# Test_Bench.net
KiCad netlist of a schematic drawn in EAGLE
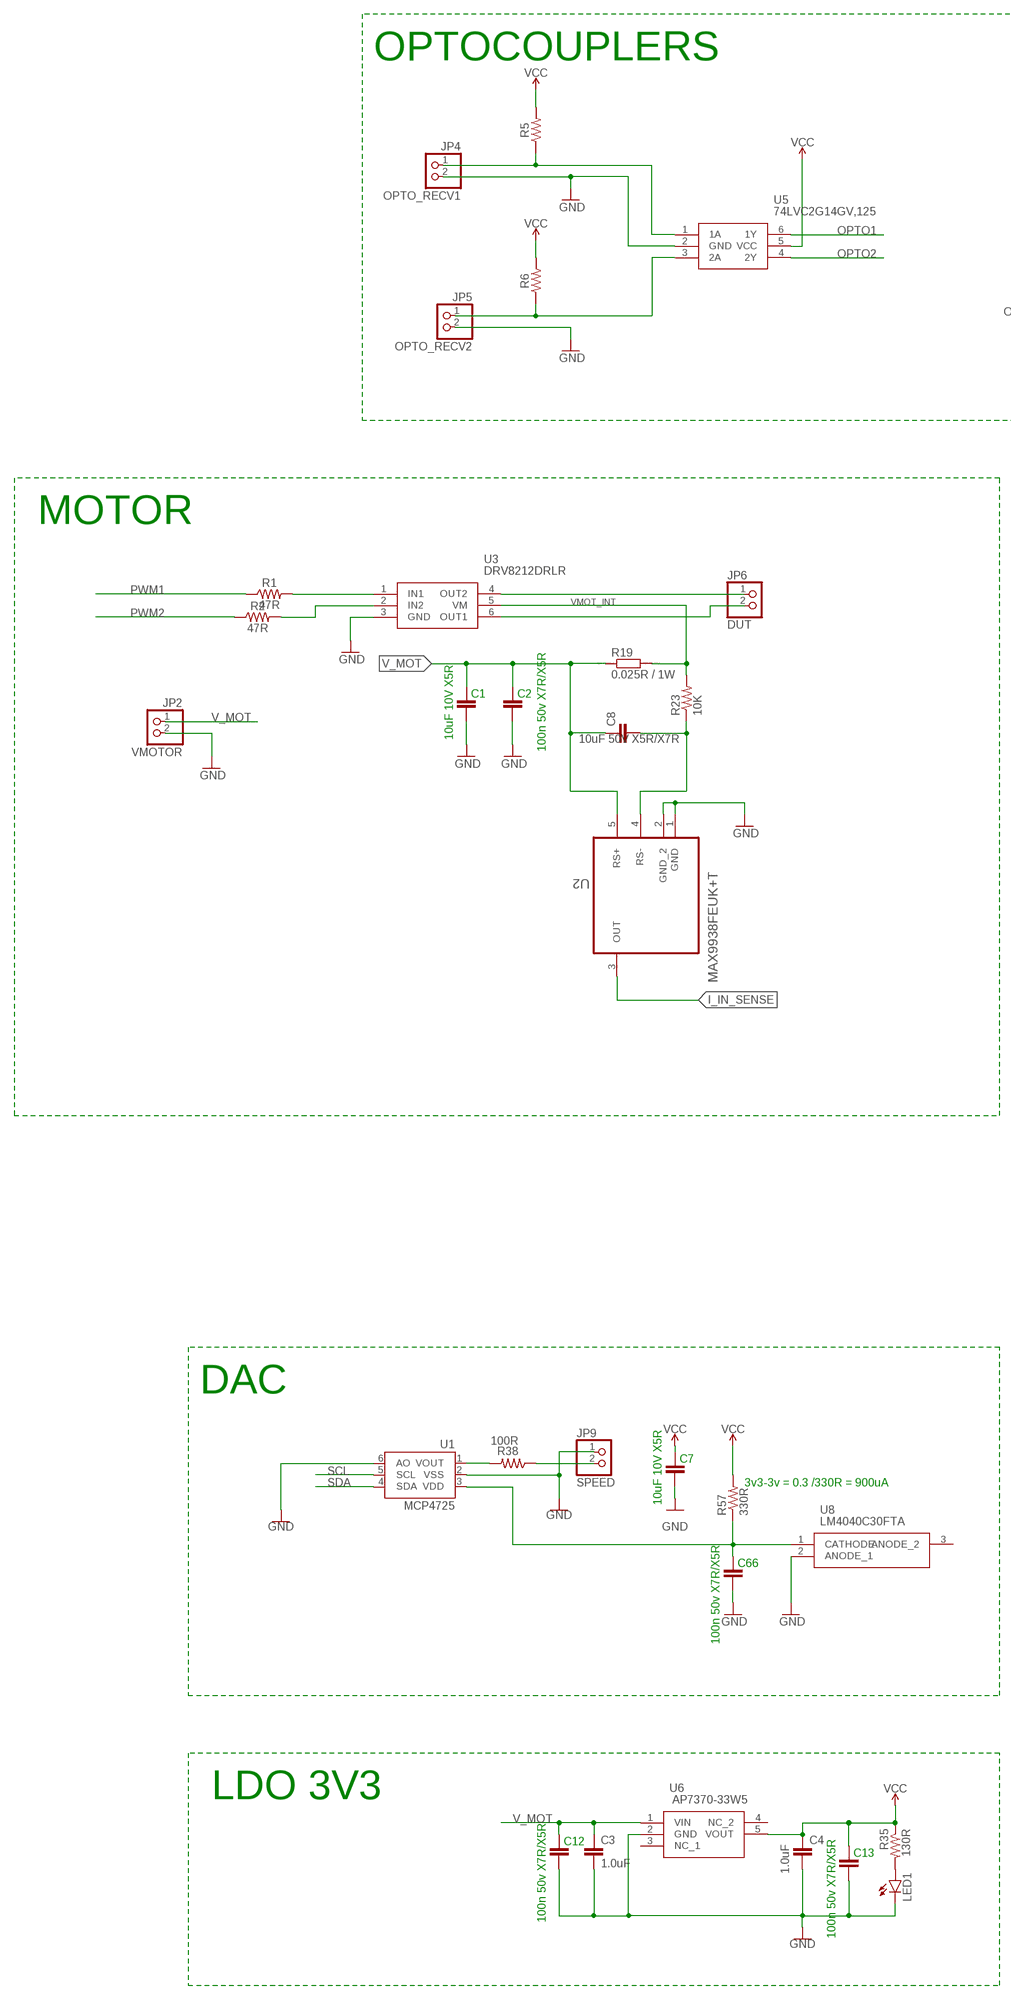
[diagram p0: schematic, sheet 1, part 1 of 2]
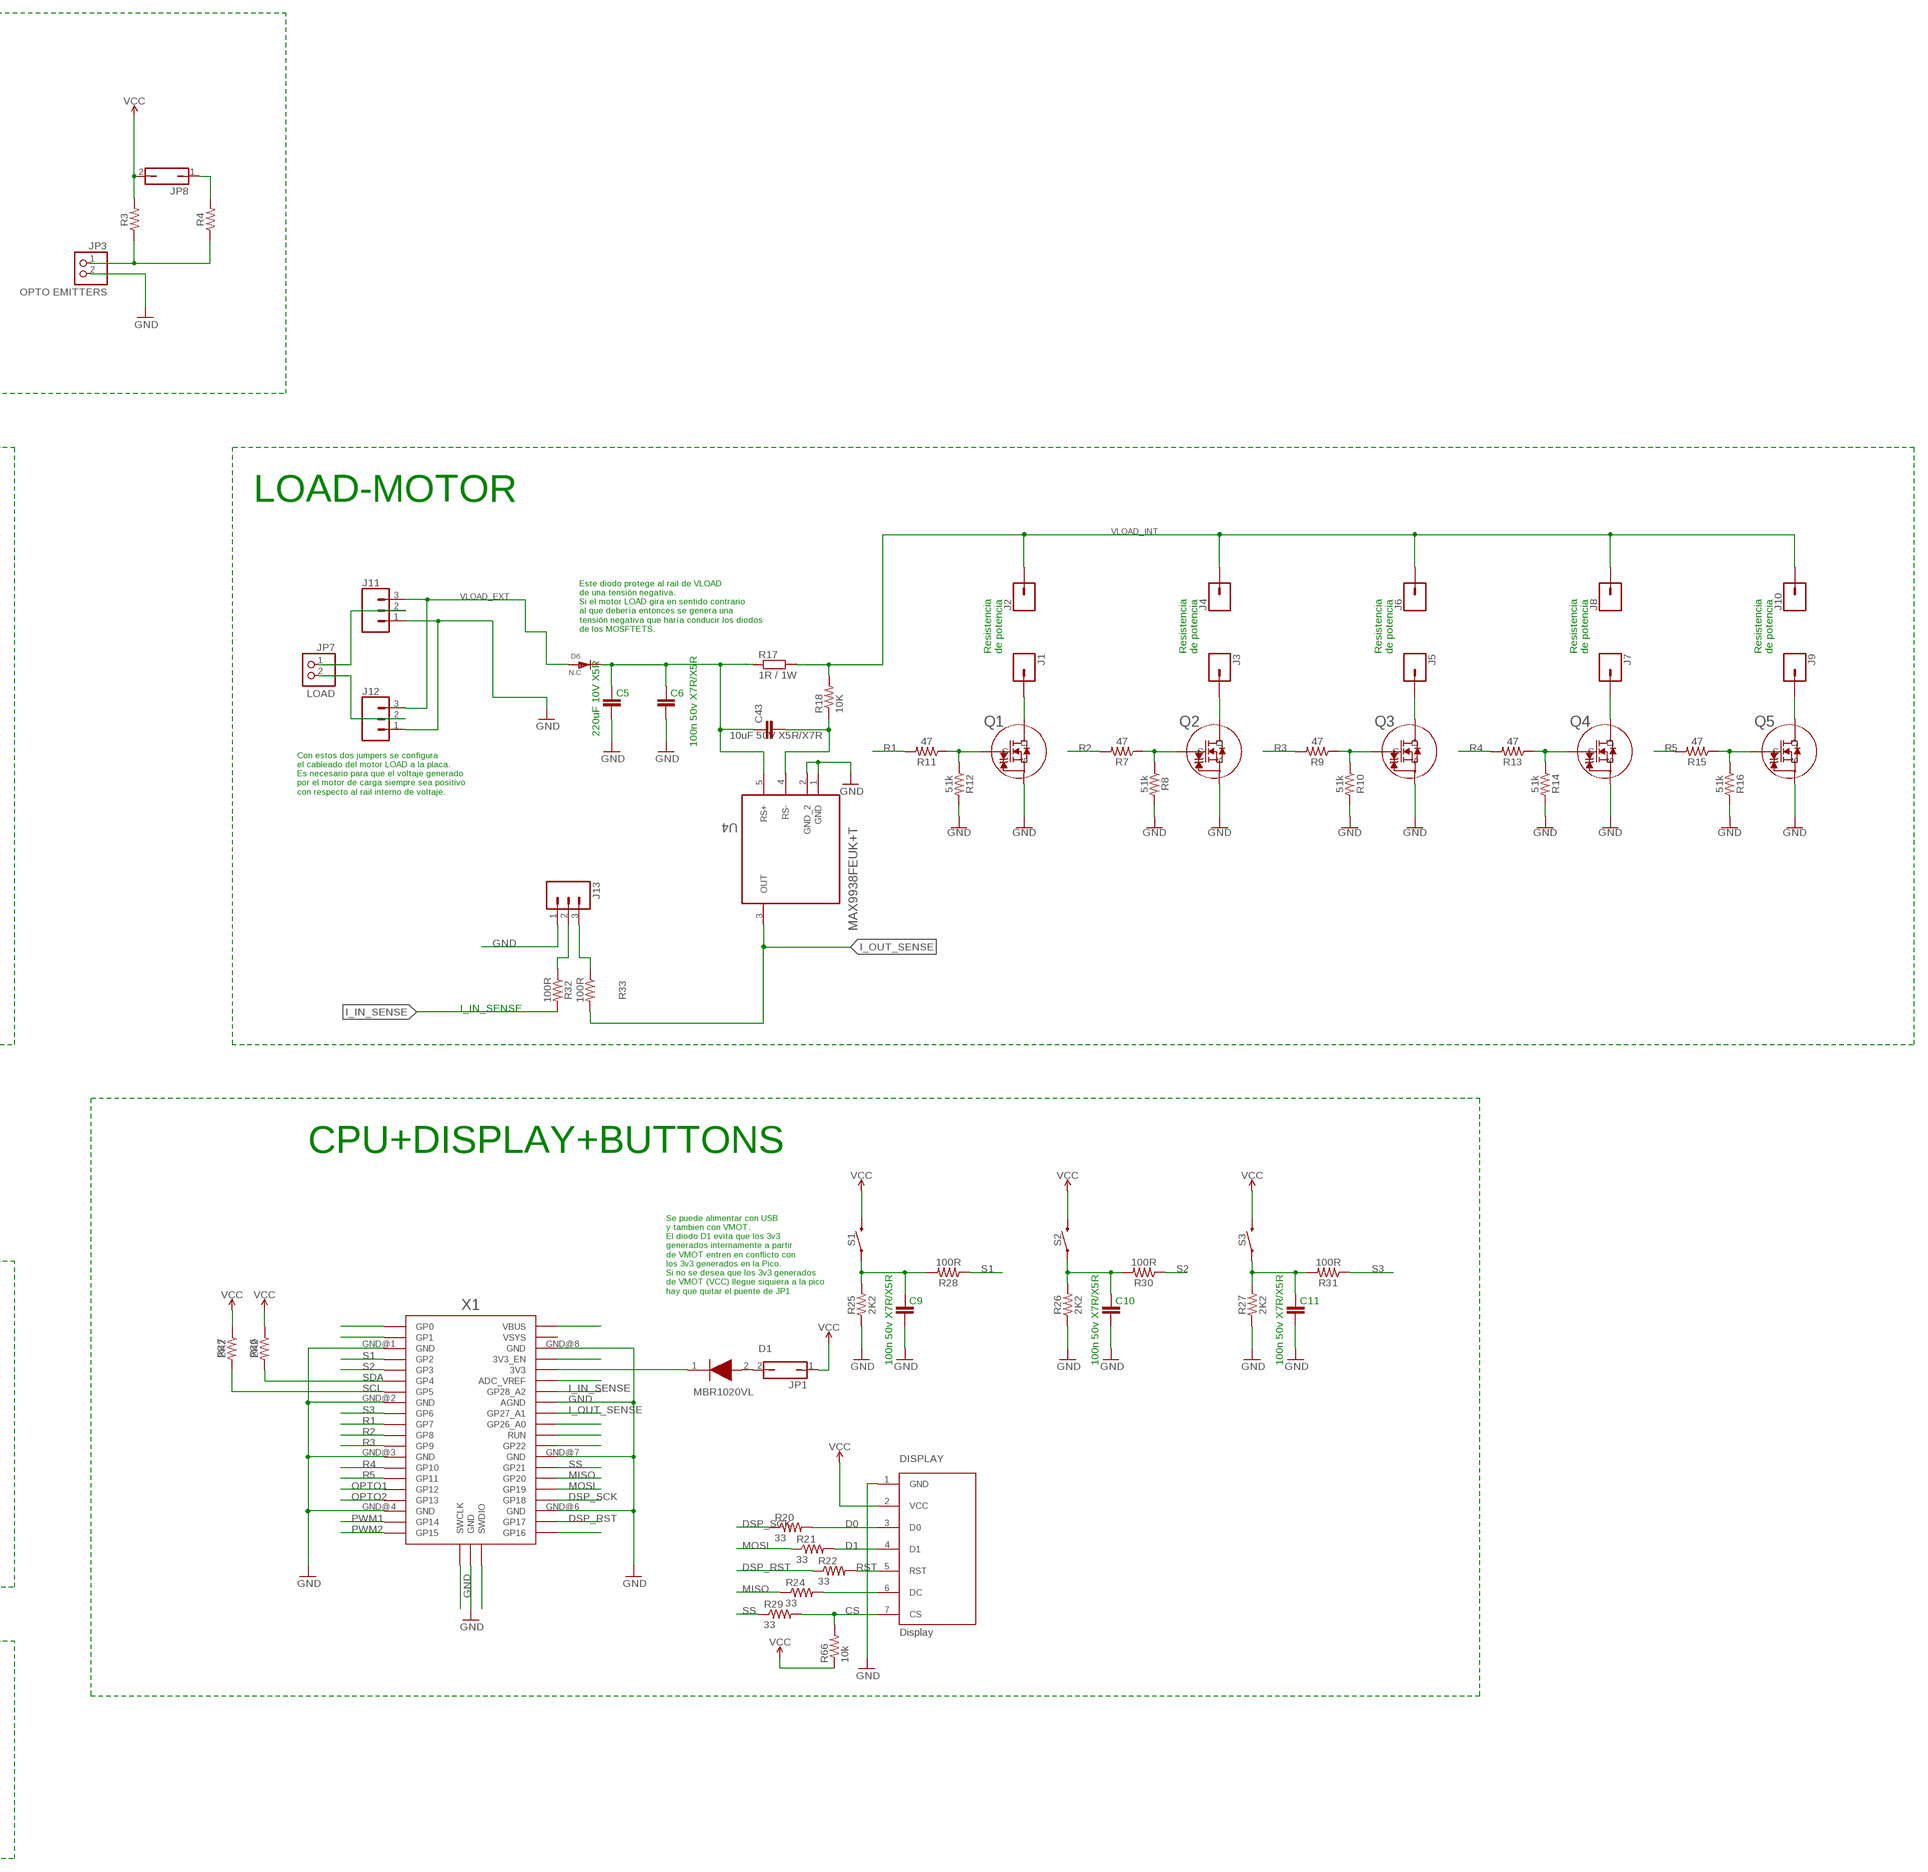
[diagram p1: schematic, sheet 1, part 2 of 2]

(export (version "E")
  (design (tool "Eeschema 10.0.6"))
  (components
    (comp (ref "C1")
      (value "10uF 10V X5R")
      (footprint "eagle-import:0805")
      (libsource (lib "eagle-import") (part "CAP0805"))
    )
    (comp (ref "C2")
      (value "100n 50v X7R/X5R")
      (footprint "eagle-import:0805")
      (libsource (lib "eagle-import") (part "CAP0805"))
    )
    (comp (ref "C3")
      (value "1.0uF")
      (footprint "eagle-import:0805")
      (libsource (lib "eagle-import") (part "1.0UF-0805-25V-(+80/-20%)"))
    )
    (comp (ref "C4")
      (value "1.0uF")
      (footprint "eagle-import:0805")
      (libsource (lib "eagle-import") (part "1.0UF-0805-25V-(+80/-20%)"))
    )
    (comp (ref "C5")
      (value "220uF 10V X5R")
      (footprint "eagle-import:0805")
      (libsource (lib "eagle-import") (part "CAP0805"))
    )
    (comp (ref "C6")
      (value "100n 50v X7R/X5R")
      (footprint "eagle-import:0805")
      (libsource (lib "eagle-import") (part "CAP0805"))
    )
    (comp (ref "C7")
      (value "10uF 10V X5R")
      (footprint "eagle-import:0805")
      (libsource (lib "eagle-import") (part "CAP0805"))
    )
    (comp (ref "C8")
      (value "10uF 50V X5R/X7R")
      (footprint "eagle-import:1206")
      (libsource (lib "eagle-import") (part "CAP1206"))
    )
    (comp (ref "C9")
      (value "100n 50v X7R/X5R")
      (footprint "eagle-import:0805")
      (libsource (lib "eagle-import") (part "CAP0805"))
    )
    (comp (ref "C10")
      (value "100n 50v X7R/X5R")
      (footprint "eagle-import:0805")
      (libsource (lib "eagle-import") (part "CAP0805"))
    )
    (comp (ref "C11")
      (value "100n 50v X7R/X5R")
      (footprint "eagle-import:0805")
      (libsource (lib "eagle-import") (part "CAP0805"))
    )
    (comp (ref "C12")
      (value "100n 50v X7R/X5R")
      (footprint "eagle-import:0805")
      (libsource (lib "eagle-import") (part "CAP0805"))
    )
    (comp (ref "C13")
      (value "100n 50v X7R/X5R")
      (footprint "eagle-import:0805")
      (libsource (lib "eagle-import") (part "CAP0805"))
    )
    (comp (ref "C43")
      (value "10uF 50V X5R/X7R")
      (footprint "eagle-import:1206")
      (libsource (lib "eagle-import") (part "CAP1206"))
    )
    (comp (ref "C66")
      (value "100n 50v X7R/X5R")
      (footprint "eagle-import:0805")
      (libsource (lib "eagle-import") (part "CAP0805"))
    )
    (comp (ref "D1")
      (value "MBR1020VL")
      (footprint "eagle-import:SODFL3617X108N")
      (fields (field (name "MOUSER_PART_NUMBER") "512-MBR1020VL"))
      (libsource (lib "eagle-import") (part "MBR1020VL"))
    )
    (comp (ref "D6")
      (value "N.C")
      (footprint "eagle-import:DO-214AB")
      (libsource (lib "eagle-import") (part "DSMC"))
    )
    (comp (ref "DISPLAY")
      (value "Display")
      (footprint "eagle-import:OLED_LCD")
      (libsource (lib "eagle-import") (part "OLED_LCD"))
    )
    (comp (ref "J1")
      (value "CONN_01")
      (footprint "eagle-import:1X01")
      (libsource (lib "eagle-import") (part "CONN_01"))
    )
    (comp (ref "J2")
      (value "CONN_01")
      (footprint "eagle-import:1X01")
      (libsource (lib "eagle-import") (part "CONN_01"))
    )
    (comp (ref "J3")
      (value "CONN_01")
      (footprint "eagle-import:1X01")
      (libsource (lib "eagle-import") (part "CONN_01"))
    )
    (comp (ref "J4")
      (value "CONN_01")
      (footprint "eagle-import:1X01")
      (libsource (lib "eagle-import") (part "CONN_01"))
    )
    (comp (ref "J5")
      (value "CONN_01")
      (footprint "eagle-import:1X01")
      (libsource (lib "eagle-import") (part "CONN_01"))
    )
    (comp (ref "J6")
      (value "CONN_01")
      (footprint "eagle-import:1X01")
      (libsource (lib "eagle-import") (part "CONN_01"))
    )
    (comp (ref "J7")
      (value "CONN_01")
      (footprint "eagle-import:1X01")
      (libsource (lib "eagle-import") (part "CONN_01"))
    )
    (comp (ref "J8")
      (value "CONN_01")
      (footprint "eagle-import:1X01")
      (libsource (lib "eagle-import") (part "CONN_01"))
    )
    (comp (ref "J9")
      (value "CONN_01")
      (footprint "eagle-import:1X01")
      (libsource (lib "eagle-import") (part "CONN_01"))
    )
    (comp (ref "J10")
      (value "CONN_01")
      (footprint "eagle-import:1X01")
      (libsource (lib "eagle-import") (part "CONN_01"))
    )
    (comp (ref "J11")
      (value "CONN_03")
      (footprint "eagle-import:1X03")
      (libsource (lib "eagle-import") (part "CONN_03"))
    )
    (comp (ref "J12")
      (value "CONN_03")
      (footprint "eagle-import:1X03")
      (libsource (lib "eagle-import") (part "CONN_03"))
    )
    (comp (ref "J13")
      (value "CONN_03")
      (footprint "eagle-import:1X03")
      (libsource (lib "eagle-import") (part "CONN_03"))
    )
    (comp (ref "JP1")
      (value "JP1Q")
      (footprint "eagle-import:JP1")
      (libsource (lib "eagle-import") (part "JP1Q"))
    )
    (comp (ref "JP2")
      (value "VMOTOR")
      (footprint "eagle-import:1X02")
      (fields (field (name "MANUFACTURER") "Generic"))
      (libsource (lib "eagle-import") (part "PINHD-1X2"))
    )
    (comp (ref "JP3")
      (value "OPTO EMITTERS")
      (footprint "eagle-import:1X02")
      (fields (field (name "MANUFACTURER") "Generic"))
      (libsource (lib "eagle-import") (part "PINHD-1X2"))
    )
    (comp (ref "JP4")
      (value "OPTO_RECV1")
      (footprint "eagle-import:1X02")
      (fields (field (name "MANUFACTURER") "Generic"))
      (libsource (lib "eagle-import") (part "PINHD-1X2"))
    )
    (comp (ref "JP5")
      (value "OPTO_RECV2")
      (footprint "eagle-import:1X02")
      (fields (field (name "MANUFACTURER") "Generic"))
      (libsource (lib "eagle-import") (part "PINHD-1X2"))
    )
    (comp (ref "JP6")
      (value "DUT")
      (footprint "eagle-import:1X02")
      (fields (field (name "MANUFACTURER") "Generic"))
      (libsource (lib "eagle-import") (part "PINHD-1X2"))
    )
    (comp (ref "JP7")
      (value "LOAD")
      (footprint "eagle-import:1X02")
      (fields (field (name "MANUFACTURER") "Generic"))
      (libsource (lib "eagle-import") (part "PINHD-1X2"))
    )
    (comp (ref "JP8")
      (value "JP1Q")
      (footprint "eagle-import:JP1")
      (libsource (lib "eagle-import") (part "JP1Q"))
    )
    (comp (ref "JP9")
      (value "SPEED")
      (footprint "eagle-import:1X02")
      (fields (field (name "MANUFACTURER") "Generic"))
      (libsource (lib "eagle-import") (part "PINHD-1X2"))
    )
    (comp (ref "LED1")
      (value "LED3MM")
      (footprint "eagle-import:LED3MM")
      (libsource (lib "eagle-import") (part "LED3MM"))
    )
    (comp (ref "Q1")
      (value "PJA3416AE_R1_00001")
      (footprint "eagle-import:SOT23_PJA3416_PNJ")
      (fields (field (name "COPYRIGHT") "Copyright (C) 2022 Ultra Librarian. All rights reserved."))
      (libsource (lib "eagle-import") (part "PJA3416AE_R1_00001"))
    )
    (comp (ref "Q2")
      (value "PJA3416AE_R1_00001")
      (footprint "eagle-import:SOT23_PJA3416_PNJ")
      (fields (field (name "COPYRIGHT") "Copyright (C) 2022 Ultra Librarian. All rights reserved."))
      (libsource (lib "eagle-import") (part "PJA3416AE_R1_00001"))
    )
    (comp (ref "Q3")
      (value "PJA3416AE_R1_00001")
      (footprint "eagle-import:SOT23_PJA3416_PNJ")
      (fields (field (name "COPYRIGHT") "Copyright (C) 2022 Ultra Librarian. All rights reserved."))
      (libsource (lib "eagle-import") (part "PJA3416AE_R1_00001"))
    )
    (comp (ref "Q4")
      (value "PJA3416AE_R1_00001")
      (footprint "eagle-import:SOT23_PJA3416_PNJ")
      (fields (field (name "COPYRIGHT") "Copyright (C) 2022 Ultra Librarian. All rights reserved."))
      (libsource (lib "eagle-import") (part "PJA3416AE_R1_00001"))
    )
    (comp (ref "Q5")
      (value "PJA3416AE_R1_00001")
      (footprint "eagle-import:SOT23_PJA3416_PNJ")
      (fields (field (name "COPYRIGHT") "Copyright (C) 2022 Ultra Librarian. All rights reserved."))
      (libsource (lib "eagle-import") (part "PJA3416AE_R1_00001"))
    )
    (comp (ref "R1")
      (value "47R")
      (footprint "eagle-import:0805")
      (libsource (lib "eagle-import") (part "RESISTOR0805"))
    )
    (comp (ref "R2")
      (value "47R")
      (footprint "eagle-import:0805")
      (libsource (lib "eagle-import") (part "RESISTOR0805"))
    )
    (comp (ref "R3")
      (value "RESISTOR0805")
      (footprint "eagle-import:0805")
      (libsource (lib "eagle-import") (part "RESISTOR0805"))
    )
    (comp (ref "R4")
      (value "RESISTOR0805")
      (footprint "eagle-import:0805")
      (libsource (lib "eagle-import") (part "RESISTOR0805"))
    )
    (comp (ref "R5")
      (value "RESISTOR0805")
      (footprint "eagle-import:0805")
      (libsource (lib "eagle-import") (part "RESISTOR0805"))
    )
    (comp (ref "R6")
      (value "RESISTOR0805")
      (footprint "eagle-import:0805")
      (libsource (lib "eagle-import") (part "RESISTOR0805"))
    )
    (comp (ref "R7")
      (value "47")
      (footprint "eagle-import:0805")
      (libsource (lib "eagle-import") (part "RESISTOR0805"))
    )
    (comp (ref "R8")
      (value "51k")
      (footprint "eagle-import:0805")
      (libsource (lib "eagle-import") (part "RESISTOR0805"))
    )
    (comp (ref "R9")
      (value "47")
      (footprint "eagle-import:0805")
      (libsource (lib "eagle-import") (part "RESISTOR0805"))
    )
    (comp (ref "R10")
      (value "51k")
      (footprint "eagle-import:0805")
      (libsource (lib "eagle-import") (part "RESISTOR0805"))
    )
    (comp (ref "R11")
      (value "47")
      (footprint "eagle-import:0805")
      (libsource (lib "eagle-import") (part "RESISTOR0805"))
    )
    (comp (ref "R12")
      (value "51k")
      (footprint "eagle-import:0805")
      (libsource (lib "eagle-import") (part "RESISTOR0805"))
    )
    (comp (ref "R13")
      (value "47")
      (footprint "eagle-import:0805")
      (libsource (lib "eagle-import") (part "RESISTOR0805"))
    )
    (comp (ref "R14")
      (value "51k")
      (footprint "eagle-import:0805")
      (libsource (lib "eagle-import") (part "RESISTOR0805"))
    )
    (comp (ref "R15")
      (value "47")
      (footprint "eagle-import:0805")
      (libsource (lib "eagle-import") (part "RESISTOR0805"))
    )
    (comp (ref "R16")
      (value "51k")
      (footprint "eagle-import:0805")
      (libsource (lib "eagle-import") (part "RESISTOR0805"))
    )
    (comp (ref "R17")
      (value "1R / 1W")
      (footprint "eagle-import:R2512")
      (libsource (lib "eagle-import") (part "RR2512"))
    )
    (comp (ref "R18")
      (value "10K")
      (footprint "eagle-import:0805")
      (libsource (lib "eagle-import") (part "RESISTOR0805"))
    )
    (comp (ref "R19")
      (value "0.025R / 1W")
      (footprint "eagle-import:R2512")
      (libsource (lib "eagle-import") (part "RR2512"))
    )
    (comp (ref "R20")
      (value "33")
      (footprint "eagle-import:0805")
      (libsource (lib "eagle-import") (part "RESISTOR0805"))
    )
    (comp (ref "R21")
      (value "33")
      (footprint "eagle-import:0805")
      (libsource (lib "eagle-import") (part "RESISTOR0805"))
    )
    (comp (ref "R22")
      (value "33")
      (footprint "eagle-import:0805")
      (libsource (lib "eagle-import") (part "RESISTOR0805"))
    )
    (comp (ref "R23")
      (value "10K")
      (footprint "eagle-import:0805")
      (libsource (lib "eagle-import") (part "RESISTOR0805"))
    )
    (comp (ref "R24")
      (value "33")
      (footprint "eagle-import:0805")
      (libsource (lib "eagle-import") (part "RESISTOR0805"))
    )
    (comp (ref "R25")
      (value "2K2")
      (footprint "eagle-import:0805")
      (libsource (lib "eagle-import") (part "RESISTOR0805"))
    )
    (comp (ref "R26")
      (value "2K2")
      (footprint "eagle-import:0805")
      (libsource (lib "eagle-import") (part "RESISTOR0805"))
    )
    (comp (ref "R27")
      (value "2K2")
      (footprint "eagle-import:0805")
      (libsource (lib "eagle-import") (part "RESISTOR0805"))
    )
    (comp (ref "R28")
      (value "100R")
      (footprint "eagle-import:0805")
      (libsource (lib "eagle-import") (part "RESISTOR0805"))
    )
    (comp (ref "R29")
      (value "33")
      (footprint "eagle-import:0805")
      (libsource (lib "eagle-import") (part "RESISTOR0805"))
    )
    (comp (ref "R30")
      (value "100R")
      (footprint "eagle-import:0805")
      (libsource (lib "eagle-import") (part "RESISTOR0805"))
    )
    (comp (ref "R31")
      (value "100R")
      (footprint "eagle-import:0805")
      (libsource (lib "eagle-import") (part "RESISTOR0805"))
    )
    (comp (ref "R32")
      (value "100R")
      (footprint "eagle-import:0805")
      (libsource (lib "eagle-import") (part "RESISTOR0805"))
    )
    (comp (ref "R33")
      (value "100R")
      (footprint "eagle-import:0805")
      (libsource (lib "eagle-import") (part "RESISTOR0805"))
    )
    (comp (ref "R35")
      (value "130R")
      (footprint "eagle-import:0805")
      (libsource (lib "eagle-import") (part "RESISTOR0805"))
    )
    (comp (ref "R36")
      (value "2K2")
      (footprint "eagle-import:0805")
      (libsource (lib "eagle-import") (part "RESISTOR0805"))
    )
    (comp (ref "R37")
      (value "2K2")
      (footprint "eagle-import:0805")
      (libsource (lib "eagle-import") (part "RESISTOR0805"))
    )
    (comp (ref "R38")
      (value "100R")
      (footprint "eagle-import:0805")
      (libsource (lib "eagle-import") (part "RESISTOR0805"))
    )
    (comp (ref "R57")
      (value "330R")
      (footprint "eagle-import:0805")
      (libsource (lib "eagle-import") (part "RESISTOR0805"))
    )
    (comp (ref "R66")
      (value "10k")
      (footprint "eagle-import:0805")
      (libsource (lib "eagle-import") (part "RESISTOR0805"))
    )
    (comp (ref "S1")
      (value "MOMENTARY-SWITCH-SPST-SMD-5.2MM")
      (footprint "eagle-import:TACTILE_SWITCH_SMD_5.2MM")
      (libsource (lib "eagle-import") (part "MOMENTARY-SWITCH-SPST-SMD-5.2MM"))
    )
    (comp (ref "S2")
      (value "MOMENTARY-SWITCH-SPST-SMD-5.2MM")
      (footprint "eagle-import:TACTILE_SWITCH_SMD_5.2MM")
      (libsource (lib "eagle-import") (part "MOMENTARY-SWITCH-SPST-SMD-5.2MM"))
    )
    (comp (ref "S3")
      (value "MOMENTARY-SWITCH-SPST-SMD-5.2MM")
      (footprint "eagle-import:TACTILE_SWITCH_SMD_5.2MM")
      (libsource (lib "eagle-import") (part "MOMENTARY-SWITCH-SPST-SMD-5.2MM"))
    )
    (comp (ref "U1")
      (value "MCP4725")
      (footprint "eagle-import:SOT23-6")
      (libsource (lib "eagle-import") (part "MCP4725SOT-23"))
    )
    (comp (ref "U2")
      (value "MAX9938FEUK+T")
      (footprint "eagle-import:SOT95P280X145-5N")
      (libsource (lib "eagle-import") (part "MAX9938FEUK+T"))
    )
    (comp (ref "U3")
      (value "DRV8212DRLR")
      (footprint "eagle-import:SOTFL50P160X60-6N")
      (fields (field (name "MOUSER_PART_NUMBER") "595-DRV8212DRLR"))
      (libsource (lib "eagle-import") (part "DRV8212DRLR"))
    )
    (comp (ref "U4")
      (value "MAX9938FEUK+T")
      (footprint "eagle-import:SOT95P280X145-5N")
      (libsource (lib "eagle-import") (part "MAX9938FEUK+T"))
    )
    (comp (ref "U5")
      (value "74LVC2G14GV,125")
      (footprint "eagle-import:SOT95P275X110-6N")
      (fields (field (name "MOUSER_PART_NUMBER") "771-LVC2G14GV125"))
      (libsource (lib "eagle-import") (part "74LVC2G14GV,125"))
    )
    (comp (ref "U6")
      (value "AP7370-33W5")
      (footprint "eagle-import:SOT95P285X140-5N")
      (fields
        (field (name "ARROW_PART_NUMBER") "AP7370-50W5-7")
        (field (name "MOUSER_PART_NUMBER") "621-AP7370-50W5-7")
      )
      (libsource (lib "eagle-import") (part "AP7370-50W5-7"))
    )
    (comp (ref "U8")
      (value "LM4040C30FTA")
      (footprint "eagle-import:SOT96P240X120-3N")
      (fields (field (name "MOUSER_PART_NUMBER") "621-LM4040C30FTA"))
      (libsource (lib "eagle-import") (part "LM4040C30FTA"))
    )
    (comp (ref "X1")
      (value "RPI_PICO_IG-TH")
      (footprint "eagle-import:RPI_PICO_TH")
      (libsource (lib "eagle-import") (part "RPI_PICO_IG-TH"))
    )
  )
  (nets
    (net (code "1") (name "/CS") (class "Default")
      (node (ref "DISPLAY") (pin "7") (pinfunction "CS_7") (pintype "bidirectional"))
      (node (ref "R29") (pin "2") (pinfunction "2_2") (pintype "passive"))
      (node (ref "R66") (pin "2") (pinfunction "2_2") (pintype "passive"))
    )
    (net (code "2") (name "/D0") (class "Default")
      (node (ref "DISPLAY") (pin "3") (pinfunction "D0_3") (pintype "bidirectional"))
      (node (ref "R20") (pin "2") (pinfunction "2_2") (pintype "passive"))
    )
    (net (code "3") (name "/D1") (class "Default")
      (node (ref "DISPLAY") (pin "4") (pinfunction "D1_4") (pintype "bidirectional"))
      (node (ref "R21") (pin "2") (pinfunction "2_2") (pintype "passive"))
    )
    (net (code "4") (name "/DSP_RST") (class "Default")
      (node (ref "R22") (pin "1") (pinfunction "1_1") (pintype "passive"))
      (node (ref "X1") (pin "GP17") (pinfunction "GP17_GP17") (pintype "bidirectional"))
    )
    (net (code "5") (name "/DSP_SCK") (class "Default")
      (node (ref "R20") (pin "1") (pinfunction "1_1") (pintype "passive"))
      (node (ref "X1") (pin "GP18") (pinfunction "GP18_GP18") (pintype "bidirectional"))
    )
    (net (code "6") (name "/MISO") (class "Default")
      (node (ref "R24") (pin "1") (pinfunction "1_1") (pintype "passive"))
      (node (ref "X1") (pin "GP20") (pinfunction "GP20_GP20") (pintype "bidirectional"))
    )
    (net (code "7") (name "/MOSI") (class "Default")
      (node (ref "R21") (pin "1") (pinfunction "1_1") (pintype "passive"))
      (node (ref "X1") (pin "GP19") (pinfunction "GP19_GP19") (pintype "bidirectional"))
    )
    (net (code "8") (name "/OPTO1") (class "Default")
      (node (ref "U5") (pin "6") (pinfunction "1Y_6") (pintype "bidirectional"))
      (node (ref "X1") (pin "GP12") (pinfunction "GP12_GP12") (pintype "bidirectional"))
    )
    (net (code "9") (name "/OPTO2") (class "Default")
      (node (ref "U5") (pin "4") (pinfunction "2Y_4") (pintype "bidirectional"))
      (node (ref "X1") (pin "GP13") (pinfunction "GP13_GP13") (pintype "bidirectional"))
    )
    (net (code "10") (name "/PWM1") (class "Default")
      (node (ref "R1") (pin "1") (pinfunction "1_1") (pintype "passive"))
      (node (ref "X1") (pin "GP14") (pinfunction "GP14_GP14") (pintype "bidirectional"))
    )
    (net (code "11") (name "/PWM2") (class "Default")
      (node (ref "R2") (pin "1") (pinfunction "1_1") (pintype "passive"))
      (node (ref "X1") (pin "GP15") (pinfunction "GP15_GP15") (pintype "bidirectional"))
    )
    (net (code "12") (name "/R1") (class "Default")
      (node (ref "R11") (pin "2") (pinfunction "2_2") (pintype "passive"))
      (node (ref "X1") (pin "GP7") (pinfunction "GP7_GP7") (pintype "bidirectional"))
    )
    (net (code "13") (name "/R2") (class "Default")
      (node (ref "R7") (pin "2") (pinfunction "2_2") (pintype "passive"))
      (node (ref "X1") (pin "GP8") (pinfunction "GP8_GP8") (pintype "bidirectional"))
    )
    (net (code "14") (name "/R3") (class "Default")
      (node (ref "R9") (pin "2") (pinfunction "2_2") (pintype "passive"))
      (node (ref "X1") (pin "GP9") (pinfunction "GP9_GP9") (pintype "bidirectional"))
    )
    (net (code "15") (name "/R4") (class "Default")
      (node (ref "R13") (pin "2") (pinfunction "2_2") (pintype "passive"))
      (node (ref "X1") (pin "GP10") (pinfunction "GP10_GP10") (pintype "bidirectional"))
    )
    (net (code "16") (name "/R5") (class "Default")
      (node (ref "R15") (pin "2") (pinfunction "2_2") (pintype "passive"))
      (node (ref "X1") (pin "GP11") (pinfunction "GP11_GP11") (pintype "bidirectional"))
    )
    (net (code "17") (name "/RST") (class "Default")
      (node (ref "DISPLAY") (pin "5") (pinfunction "RST_5") (pintype "bidirectional"))
      (node (ref "R22") (pin "2") (pinfunction "2_2") (pintype "passive"))
    )
    (net (code "18") (name "/S1") (class "Default")
      (node (ref "R28") (pin "1") (pinfunction "1_1") (pintype "passive"))
      (node (ref "X1") (pin "GP2") (pinfunction "GP2_GP2") (pintype "bidirectional"))
    )
    (net (code "19") (name "/S2") (class "Default")
      (node (ref "R30") (pin "1") (pinfunction "1_1") (pintype "passive"))
      (node (ref "X1") (pin "GP3") (pinfunction "GP3_GP3") (pintype "bidirectional"))
    )
    (net (code "20") (name "/S3") (class "Default")
      (node (ref "R31") (pin "1") (pinfunction "1_1") (pintype "passive"))
      (node (ref "X1") (pin "GP6") (pinfunction "GP6_GP6") (pintype "bidirectional"))
    )
    (net (code "21") (name "/SCL") (class "Default")
      (node (ref "R37") (pin "2") (pinfunction "2_2") (pintype "passive"))
      (node (ref "U1") (pin "5") (pinfunction "SCL_5") (pintype "bidirectional"))
      (node (ref "X1") (pin "GP5") (pinfunction "GP5_GP5") (pintype "bidirectional"))
    )
    (net (code "22") (name "/SDA") (class "Default")
      (node (ref "R36") (pin "2") (pinfunction "2_2") (pintype "passive"))
      (node (ref "U1") (pin "4") (pinfunction "SDA_4") (pintype "bidirectional"))
      (node (ref "X1") (pin "GP4") (pinfunction "GP4_GP4") (pintype "bidirectional"))
    )
    (net (code "23") (name "/SS") (class "Default")
      (node (ref "R29") (pin "1") (pinfunction "1_1") (pintype "passive"))
      (node (ref "X1") (pin "GP21") (pinfunction "GP21_GP21") (pintype "bidirectional"))
    )
    (net (code "24") (name "/VLOAD_EXT") (class "Default")
      (node (ref "D6") (pin "1") (pinfunction "A_1") (pintype "bidirectional"))
      (node (ref "J11") (pin "3") (pinfunction "3_3") (pintype "passive"))
      (node (ref "J12") (pin "3") (pinfunction "3_3") (pintype "passive"))
    )
    (net (code "25") (name "/VLOAD_INT") (class "Default")
      (node (ref "J10") (pin "1") (pinfunction "1_1") (pintype "passive"))
      (node (ref "J2") (pin "1") (pinfunction "1_1") (pintype "passive"))
      (node (ref "J4") (pin "1") (pinfunction "1_1") (pintype "passive"))
      (node (ref "J6") (pin "1") (pinfunction "1_1") (pintype "passive"))
      (node (ref "J8") (pin "1") (pinfunction "1_1") (pintype "passive"))
      (node (ref "R17") (pin "2") (pinfunction "2_2") (pintype "passive"))
      (node (ref "R18") (pin "2") (pinfunction "2_2") (pintype "passive"))
    )
    (net (code "26") (name "/VMOT_INT") (class "Default")
      (node (ref "R19") (pin "2") (pinfunction "2_2") (pintype "passive"))
      (node (ref "R23") (pin "2") (pinfunction "2_2") (pintype "passive"))
      (node (ref "U3") (pin "5") (pinfunction "VM_5") (pintype "bidirectional"))
    )
    (net (code "27") (name "GND") (class "Default")
      (node (ref "C1") (pin "1") (pinfunction "1_1") (pintype "passive"))
      (node (ref "C10") (pin "1") (pinfunction "1_1") (pintype "passive"))
      (node (ref "C11") (pin "1") (pinfunction "1_1") (pintype "passive"))
      (node (ref "C12") (pin "1") (pinfunction "1_1") (pintype "passive"))
      (node (ref "C13") (pin "1") (pinfunction "1_1") (pintype "passive"))
      (node (ref "C2") (pin "1") (pinfunction "1_1") (pintype "passive"))
      (node (ref "C3") (pin "2") (pinfunction "2_2") (pintype "passive"))
      (node (ref "C4") (pin "2") (pinfunction "2_2") (pintype "passive"))
      (node (ref "C5") (pin "1") (pinfunction "1_1") (pintype "passive"))
      (node (ref "C6") (pin "1") (pinfunction "1_1") (pintype "passive"))
      (node (ref "C66") (pin "1") (pinfunction "1_1") (pintype "passive"))
      (node (ref "C7") (pin "1") (pinfunction "1_1") (pintype "passive"))
      (node (ref "C9") (pin "1") (pinfunction "1_1") (pintype "passive"))
      (node (ref "DISPLAY") (pin "1") (pinfunction "GND_1") (pintype "bidirectional"))
      (node (ref "J11") (pin "1") (pinfunction "1_1") (pintype "passive"))
      (node (ref "J12") (pin "1") (pinfunction "1_1") (pintype "passive"))
      (node (ref "J13") (pin "1") (pinfunction "1_1") (pintype "passive"))
      (node (ref "JP2") (pin "2") (pinfunction "2_2") (pintype "passive"))
      (node (ref "JP3") (pin "2") (pinfunction "2_2") (pintype "passive"))
      (node (ref "JP4") (pin "2") (pinfunction "2_2") (pintype "passive"))
      (node (ref "JP5") (pin "2") (pinfunction "2_2") (pintype "passive"))
      (node (ref "JP9") (pin "1") (pinfunction "1_1") (pintype "passive"))
      (node (ref "LED1") (pin "K") (pinfunction "C_K") (pintype "passive"))
      (node (ref "Q1") (pin "2") (pinfunction "S_2") (pintype "passive"))
      (node (ref "Q2") (pin "2") (pinfunction "S_2") (pintype "passive"))
      (node (ref "Q3") (pin "2") (pinfunction "S_2") (pintype "passive"))
      (node (ref "Q4") (pin "2") (pinfunction "S_2") (pintype "passive"))
      (node (ref "Q5") (pin "2") (pinfunction "S_2") (pintype "passive"))
      (node (ref "R10") (pin "2") (pinfunction "2_2") (pintype "passive"))
      (node (ref "R12") (pin "2") (pinfunction "2_2") (pintype "passive"))
      (node (ref "R14") (pin "2") (pinfunction "2_2") (pintype "passive"))
      (node (ref "R16") (pin "2") (pinfunction "2_2") (pintype "passive"))
      (node (ref "R25") (pin "1") (pinfunction "1_1") (pintype "passive"))
      (node (ref "R26") (pin "1") (pinfunction "1_1") (pintype "passive"))
      (node (ref "R27") (pin "1") (pinfunction "1_1") (pintype "passive"))
      (node (ref "R8") (pin "2") (pinfunction "2_2") (pintype "passive"))
      (node (ref "U1") (pin "2") (pinfunction "VSS_2") (pintype "bidirectional"))
      (node (ref "U1") (pin "6") (pinfunction "AO_6") (pintype "bidirectional"))
      (node (ref "U2") (pin "1") (pinfunction "GND_1") (pintype "passive"))
      (node (ref "U2") (pin "2") (pinfunction "GND_2_2") (pintype "passive"))
      (node (ref "U3") (pin "3") (pinfunction "GND_3") (pintype "bidirectional"))
      (node (ref "U4") (pin "1") (pinfunction "GND_1") (pintype "passive"))
      (node (ref "U4") (pin "2") (pinfunction "GND_2_2") (pintype "passive"))
      (node (ref "U5") (pin "2") (pinfunction "GND_2") (pintype "bidirectional"))
      (node (ref "U6") (pin "2") (pinfunction "GND_2") (pintype "bidirectional"))
      (node (ref "U8") (pin "2") (pinfunction "ANODE_1_2") (pintype "bidirectional"))
      (node (ref "X1") (pin "AGND") (pinfunction "AGND_AGND") (pintype "bidirectional"))
      (node (ref "X1") (pin "GND@1") (pinfunction "GND_GND@1") (pintype "bidirectional"))
      (node (ref "X1") (pin "GND@2") (pinfunction "GND_GND@2") (pintype "bidirectional"))
      (node (ref "X1") (pin "GND@3") (pinfunction "GND_GND@3") (pintype "bidirectional"))
      (node (ref "X1") (pin "GND@4") (pinfunction "GND_GND@4") (pintype "bidirectional"))
      (node (ref "X1") (pin "GND@5") (pinfunction "GND_GND@5") (pintype "bidirectional"))
      (node (ref "X1") (pin "GND@6") (pinfunction "GND_GND@6") (pintype "bidirectional"))
      (node (ref "X1") (pin "GND@7") (pinfunction "GND_GND@7") (pintype "bidirectional"))
      (node (ref "X1") (pin "GND@8") (pinfunction "GND_GND@8") (pintype "bidirectional"))
    )
    (net (code "28") (name "I_IN_SENSE") (class "Default")
      (node (ref "R32") (pin "2") (pinfunction "2_2") (pintype "passive"))
      (node (ref "U2") (pin "3") (pinfunction "OUT_3") (pintype "output"))
      (node (ref "X1") (pin "GP28_A2") (pinfunction "GP28_A2_GP28_A2") (pintype "bidirectional"))
    )
    (net (code "29") (name "I_OUT_SENSE") (class "Default")
      (node (ref "R33") (pin "2") (pinfunction "2_2") (pintype "passive"))
      (node (ref "U4") (pin "3") (pinfunction "OUT_3") (pintype "output"))
      (node (ref "X1") (pin "GP27_A1") (pinfunction "GP27_A1_GP27_A1") (pintype "bidirectional"))
    )
    (net (code "30") (name "Net-(C9-Pad2)") (class "Default")
      (node (ref "C9") (pin "2") (pinfunction "2_2") (pintype "passive"))
      (node (ref "R25") (pin "2") (pinfunction "2_2") (pintype "passive"))
      (node (ref "R28") (pin "2") (pinfunction "2_2") (pintype "passive"))
      (node (ref "S1") (pin "1") (pinfunction "1_1") (pintype "passive"))
    )
    (net (code "31") (name "Net-(C10-Pad2)") (class "Default")
      (node (ref "C10") (pin "2") (pinfunction "2_2") (pintype "passive"))
      (node (ref "R26") (pin "2") (pinfunction "2_2") (pintype "passive"))
      (node (ref "R30") (pin "2") (pinfunction "2_2") (pintype "passive"))
      (node (ref "S2") (pin "1") (pinfunction "1_1") (pintype "passive"))
    )
    (net (code "32") (name "Net-(C11-Pad2)") (class "Default")
      (node (ref "C11") (pin "2") (pinfunction "2_2") (pintype "passive"))
      (node (ref "R27") (pin "2") (pinfunction "2_2") (pintype "passive"))
      (node (ref "R31") (pin "2") (pinfunction "2_2") (pintype "passive"))
      (node (ref "S3") (pin "1") (pinfunction "1_1") (pintype "passive"))
    )
    (net (code "33") (name "Net-(D1-A)") (class "Default")
      (node (ref "D1") (pin "2") (pinfunction "A_2") (pintype "bidirectional"))
      (node (ref "JP1") (pin "2") (pinfunction "2_2") (pintype "passive"))
    )
    (net (code "34") (name "Net-(D1-K)") (class "Default")
      (node (ref "D1") (pin "1") (pinfunction "K_1") (pintype "bidirectional"))
      (node (ref "X1") (pin "3V3") (pinfunction "3V3_3V3") (pintype "bidirectional"))
    )
    (net (code "35") (name "Net-(D6-K)") (class "Default")
      (node (ref "C43") (pin "1") (pinfunction "1_1") (pintype "passive"))
      (node (ref "C5") (pin "2") (pinfunction "2_2") (pintype "passive"))
      (node (ref "C6") (pin "2") (pinfunction "2_2") (pintype "passive"))
      (node (ref "D6") (pin "2") (pinfunction "K_2") (pintype "bidirectional"))
      (node (ref "R17") (pin "1") (pinfunction "1_1") (pintype "passive"))
      (node (ref "U4") (pin "5") (pinfunction "RS+_5") (pintype "power_in"))
    )
    (net (code "36") (name "Net-(DISPLAY-DC)") (class "Default")
      (node (ref "DISPLAY") (pin "6") (pinfunction "DC_6") (pintype "bidirectional"))
      (node (ref "R24") (pin "2") (pinfunction "2_2") (pintype "passive"))
    )
    (net (code "37") (name "Net-(J11-Pad2)") (class "Default")
      (node (ref "J11") (pin "2") (pinfunction "2_2") (pintype "passive"))
      (node (ref "JP7") (pin "1") (pinfunction "1_1") (pintype "passive"))
    )
    (net (code "38") (name "Net-(J12-Pad2)") (class "Default")
      (node (ref "J12") (pin "2") (pinfunction "2_2") (pintype "passive"))
      (node (ref "JP7") (pin "2") (pinfunction "2_2") (pintype "passive"))
    )
    (net (code "39") (name "Net-(J13-Pad2)") (class "Default")
      (node (ref "J13") (pin "2") (pinfunction "2_2") (pintype "passive"))
      (node (ref "R32") (pin "1") (pinfunction "1_1") (pintype "passive"))
    )
    (net (code "40") (name "Net-(J13-Pad3)") (class "Default")
      (node (ref "J13") (pin "3") (pinfunction "3_3") (pintype "passive"))
      (node (ref "R33") (pin "1") (pinfunction "1_1") (pintype "passive"))
    )
    (net (code "41") (name "Net-(JP3-Pad1)") (class "Default")
      (node (ref "JP3") (pin "1") (pinfunction "1_1") (pintype "passive"))
      (node (ref "R3") (pin "1") (pinfunction "1_1") (pintype "passive"))
      (node (ref "R4") (pin "1") (pinfunction "1_1") (pintype "passive"))
    )
    (net (code "42") (name "Net-(JP8-Pad1)") (class "Default")
      (node (ref "JP8") (pin "1") (pinfunction "1_1") (pintype "passive"))
      (node (ref "R4") (pin "2") (pinfunction "2_2") (pintype "passive"))
    )
    (net (code "43") (name "Net-(JP9-Pad2)") (class "Default")
      (node (ref "JP9") (pin "2") (pinfunction "2_2") (pintype "passive"))
      (node (ref "R38") (pin "1") (pinfunction "1_1") (pintype "passive"))
    )
    (net (code "44") (name "Net-(LED1-PadA)") (class "Default")
      (node (ref "LED1") (pin "A") (pinfunction "A_A") (pintype "passive"))
      (node (ref "R35") (pin "2") (pinfunction "2_2") (pintype "passive"))
    )
    (net (code "45") (name "Net-(Q1-D)") (class "Default")
      (node (ref "J1") (pin "1") (pinfunction "1_1") (pintype "passive"))
      (node (ref "Q1") (pin "3") (pinfunction "D_3") (pintype "passive"))
    )
    (net (code "46") (name "Net-(Q1-G)") (class "Default")
      (node (ref "Q1") (pin "1") (pinfunction "G_1") (pintype "passive"))
      (node (ref "R11") (pin "1") (pinfunction "1_1") (pintype "passive"))
      (node (ref "R12") (pin "1") (pinfunction "1_1") (pintype "passive"))
    )
    (net (code "47") (name "Net-(Q2-D)") (class "Default")
      (node (ref "J3") (pin "1") (pinfunction "1_1") (pintype "passive"))
      (node (ref "Q2") (pin "3") (pinfunction "D_3") (pintype "passive"))
    )
    (net (code "48") (name "Net-(Q2-G)") (class "Default")
      (node (ref "Q2") (pin "1") (pinfunction "G_1") (pintype "passive"))
      (node (ref "R7") (pin "1") (pinfunction "1_1") (pintype "passive"))
      (node (ref "R8") (pin "1") (pinfunction "1_1") (pintype "passive"))
    )
    (net (code "49") (name "Net-(Q3-D)") (class "Default")
      (node (ref "J5") (pin "1") (pinfunction "1_1") (pintype "passive"))
      (node (ref "Q3") (pin "3") (pinfunction "D_3") (pintype "passive"))
    )
    (net (code "50") (name "Net-(Q3-G)") (class "Default")
      (node (ref "Q3") (pin "1") (pinfunction "G_1") (pintype "passive"))
      (node (ref "R10") (pin "1") (pinfunction "1_1") (pintype "passive"))
      (node (ref "R9") (pin "1") (pinfunction "1_1") (pintype "passive"))
    )
    (net (code "51") (name "Net-(Q4-D)") (class "Default")
      (node (ref "J7") (pin "1") (pinfunction "1_1") (pintype "passive"))
      (node (ref "Q4") (pin "3") (pinfunction "D_3") (pintype "passive"))
    )
    (net (code "52") (name "Net-(Q4-G)") (class "Default")
      (node (ref "Q4") (pin "1") (pinfunction "G_1") (pintype "passive"))
      (node (ref "R13") (pin "1") (pinfunction "1_1") (pintype "passive"))
      (node (ref "R14") (pin "1") (pinfunction "1_1") (pintype "passive"))
    )
    (net (code "53") (name "Net-(Q5-D)") (class "Default")
      (node (ref "J9") (pin "1") (pinfunction "1_1") (pintype "passive"))
      (node (ref "Q5") (pin "3") (pinfunction "D_3") (pintype "passive"))
    )
    (net (code "54") (name "Net-(Q5-G)") (class "Default")
      (node (ref "Q5") (pin "1") (pinfunction "G_1") (pintype "passive"))
      (node (ref "R15") (pin "1") (pinfunction "1_1") (pintype "passive"))
      (node (ref "R16") (pin "1") (pinfunction "1_1") (pintype "passive"))
    )
    (net (code "55") (name "Net-(U1-VDD)") (class "Default")
      (node (ref "C66") (pin "2") (pinfunction "2_2") (pintype "passive"))
      (node (ref "R57") (pin "1") (pinfunction "1_1") (pintype "passive"))
      (node (ref "U1") (pin "3") (pinfunction "VDD_3") (pintype "bidirectional"))
      (node (ref "U8") (pin "1") (pinfunction "CATHODE_1") (pintype "bidirectional"))
    )
    (net (code "56") (name "Net-(U1-VOUT)") (class "Default")
      (node (ref "R38") (pin "2") (pinfunction "2_2") (pintype "passive"))
      (node (ref "U1") (pin "1") (pinfunction "VOUT_1") (pintype "bidirectional"))
    )
    (net (code "57") (name "Net-(U2-RS-)") (class "Default")
      (node (ref "C8") (pin "2") (pinfunction "2_2") (pintype "passive"))
      (node (ref "R23") (pin "1") (pinfunction "1_1") (pintype "passive"))
      (node (ref "U2") (pin "4") (pinfunction "RS-_4") (pintype "input"))
    )
    (net (code "58") (name "Net-(U3-IN1)") (class "Default")
      (node (ref "R1") (pin "2") (pinfunction "2_2") (pintype "passive"))
      (node (ref "U3") (pin "1") (pinfunction "IN1_1") (pintype "bidirectional"))
    )
    (net (code "59") (name "Net-(U3-IN2)") (class "Default")
      (node (ref "R2") (pin "2") (pinfunction "2_2") (pintype "passive"))
      (node (ref "U3") (pin "2") (pinfunction "IN2_2") (pintype "bidirectional"))
    )
    (net (code "60") (name "Net-(U3-OUT1)") (class "Default")
      (node (ref "JP6") (pin "2") (pinfunction "2_2") (pintype "passive"))
      (node (ref "U3") (pin "6") (pinfunction "OUT1_6") (pintype "bidirectional"))
    )
    (net (code "61") (name "Net-(U3-OUT2)") (class "Default")
      (node (ref "JP6") (pin "1") (pinfunction "1_1") (pintype "passive"))
      (node (ref "U3") (pin "4") (pinfunction "OUT2_4") (pintype "bidirectional"))
    )
    (net (code "62") (name "Net-(U4-RS-)") (class "Default")
      (node (ref "C43") (pin "2") (pinfunction "2_2") (pintype "passive"))
      (node (ref "R18") (pin "1") (pinfunction "1_1") (pintype "passive"))
      (node (ref "U4") (pin "4") (pinfunction "RS-_4") (pintype "input"))
    )
    (net (code "63") (name "Net-(U5-1A)") (class "Default")
      (node (ref "JP4") (pin "1") (pinfunction "1_1") (pintype "passive"))
      (node (ref "R5") (pin "1") (pinfunction "1_1") (pintype "passive"))
      (node (ref "U5") (pin "1") (pinfunction "1A_1") (pintype "bidirectional"))
    )
    (net (code "64") (name "Net-(U5-2A)") (class "Default")
      (node (ref "JP5") (pin "1") (pinfunction "1_1") (pintype "passive"))
      (node (ref "R6") (pin "1") (pinfunction "1_1") (pintype "passive"))
      (node (ref "U5") (pin "3") (pinfunction "2A_3") (pintype "bidirectional"))
    )
    (net (code "65") (name "VCC") (class "Default")
      (node (ref "C13") (pin "2") (pinfunction "2_2") (pintype "passive"))
      (node (ref "C4") (pin "1") (pinfunction "1_1") (pintype "passive"))
      (node (ref "C7") (pin "2") (pinfunction "2_2") (pintype "passive"))
      (node (ref "DISPLAY") (pin "2") (pinfunction "VCC_2") (pintype "bidirectional"))
      (node (ref "JP1") (pin "1") (pinfunction "1_1") (pintype "passive"))
      (node (ref "JP8") (pin "2") (pinfunction "2_2") (pintype "passive"))
      (node (ref "R3") (pin "2") (pinfunction "2_2") (pintype "passive"))
      (node (ref "R35") (pin "1") (pinfunction "1_1") (pintype "passive"))
      (node (ref "R36") (pin "1") (pinfunction "1_1") (pintype "passive"))
      (node (ref "R37") (pin "1") (pinfunction "1_1") (pintype "passive"))
      (node (ref "R5") (pin "2") (pinfunction "2_2") (pintype "passive"))
      (node (ref "R57") (pin "2") (pinfunction "2_2") (pintype "passive"))
      (node (ref "R6") (pin "2") (pinfunction "2_2") (pintype "passive"))
      (node (ref "R66") (pin "1") (pinfunction "1_1") (pintype "passive"))
      (node (ref "S1") (pin "3") (pinfunction "2_3") (pintype "passive"))
      (node (ref "S2") (pin "3") (pinfunction "2_3") (pintype "passive"))
      (node (ref "S3") (pin "3") (pinfunction "2_3") (pintype "passive"))
      (node (ref "U5") (pin "5") (pinfunction "VCC_5") (pintype "bidirectional"))
      (node (ref "U6") (pin "5") (pinfunction "VOUT_5") (pintype "bidirectional"))
    )
    (net (code "66") (name "V_MOT") (class "Default")
      (node (ref "C1") (pin "2") (pinfunction "2_2") (pintype "passive"))
      (node (ref "C12") (pin "2") (pinfunction "2_2") (pintype "passive"))
      (node (ref "C2") (pin "2") (pinfunction "2_2") (pintype "passive"))
      (node (ref "C3") (pin "1") (pinfunction "1_1") (pintype "passive"))
      (node (ref "C8") (pin "1") (pinfunction "1_1") (pintype "passive"))
      (node (ref "JP2") (pin "1") (pinfunction "1_1") (pintype "passive"))
      (node (ref "R19") (pin "1") (pinfunction "1_1") (pintype "passive"))
      (node (ref "U2") (pin "5") (pinfunction "RS+_5") (pintype "power_in"))
      (node (ref "U6") (pin "1") (pinfunction "VIN_1") (pintype "bidirectional"))
    )
    (net (code "67") (name "unconnected-(U6-NC_1-Pad3)") (class "Default")
      (node (ref "U6") (pin "3") (pinfunction "NC_1_3") (pintype "bidirectional"))
    )
    (net (code "68") (name "unconnected-(U6-NC_2-Pad4)") (class "Default")
      (node (ref "U6") (pin "4") (pinfunction "NC_2_4") (pintype "bidirectional"))
    )
    (net (code "69") (name "unconnected-(U8-ANODE_2-Pad3)") (class "Default")
      (node (ref "U8") (pin "3") (pinfunction "ANODE_2_3") (pintype "bidirectional"))
    )
    (net (code "70") (name "unconnected-(X1-Pad3V3_EN)") (class "Default")
      (node (ref "X1") (pin "3V3_EN") (pinfunction "3V3_EN_3V3_EN") (pintype "bidirectional"))
    )
    (net (code "71") (name "unconnected-(X1-PadADC_VREF)") (class "Default")
      (node (ref "X1") (pin "ADC_VREF") (pinfunction "ADC_VREF_ADC_VREF") (pintype "bidirectional"))
    )
    (net (code "72") (name "unconnected-(X1-PadGP0)") (class "Default")
      (node (ref "X1") (pin "GP0") (pinfunction "GP0_GP0") (pintype "bidirectional"))
    )
    (net (code "73") (name "unconnected-(X1-PadGP1)") (class "Default")
      (node (ref "X1") (pin "GP1") (pinfunction "GP1_GP1") (pintype "bidirectional"))
    )
    (net (code "74") (name "unconnected-(X1-PadGP16)") (class "Default")
      (node (ref "X1") (pin "GP16") (pinfunction "GP16_GP16") (pintype "bidirectional"))
    )
    (net (code "75") (name "unconnected-(X1-PadGP22)") (class "Default")
      (node (ref "X1") (pin "GP22") (pinfunction "GP22_GP22") (pintype "bidirectional"))
    )
    (net (code "76") (name "unconnected-(X1-PadGP26_A0)") (class "Default")
      (node (ref "X1") (pin "GP26_A0") (pinfunction "GP26_A0_GP26_A0") (pintype "bidirectional"))
    )
    (net (code "77") (name "unconnected-(X1-PadRUN)") (class "Default")
      (node (ref "X1") (pin "RUN") (pinfunction "RUN_RUN") (pintype "bidirectional"))
    )
    (net (code "78") (name "unconnected-(X1-PadSWCLK)") (class "Default")
      (node (ref "X1") (pin "SWCLK") (pinfunction "SWCLK_SWCLK") (pintype "bidirectional"))
    )
    (net (code "79") (name "unconnected-(X1-PadSWDIO)") (class "Default")
      (node (ref "X1") (pin "SWDIO") (pinfunction "SWDIO_SWDIO") (pintype "bidirectional"))
    )
    (net (code "80") (name "unconnected-(X1-PadVBUS)") (class "Default")
      (node (ref "X1") (pin "VBUS") (pinfunction "VBUS_VBUS") (pintype "bidirectional"))
    )
    (net (code "81") (name "unconnected-(X1-PadVSYS)") (class "Default")
      (node (ref "X1") (pin "VSYS") (pinfunction "VSYS_VSYS") (pintype "bidirectional"))
    )
  )
)
